# POWER_SUPPLY.net
KiCad netlist of a schematic drawn in Altium Designer
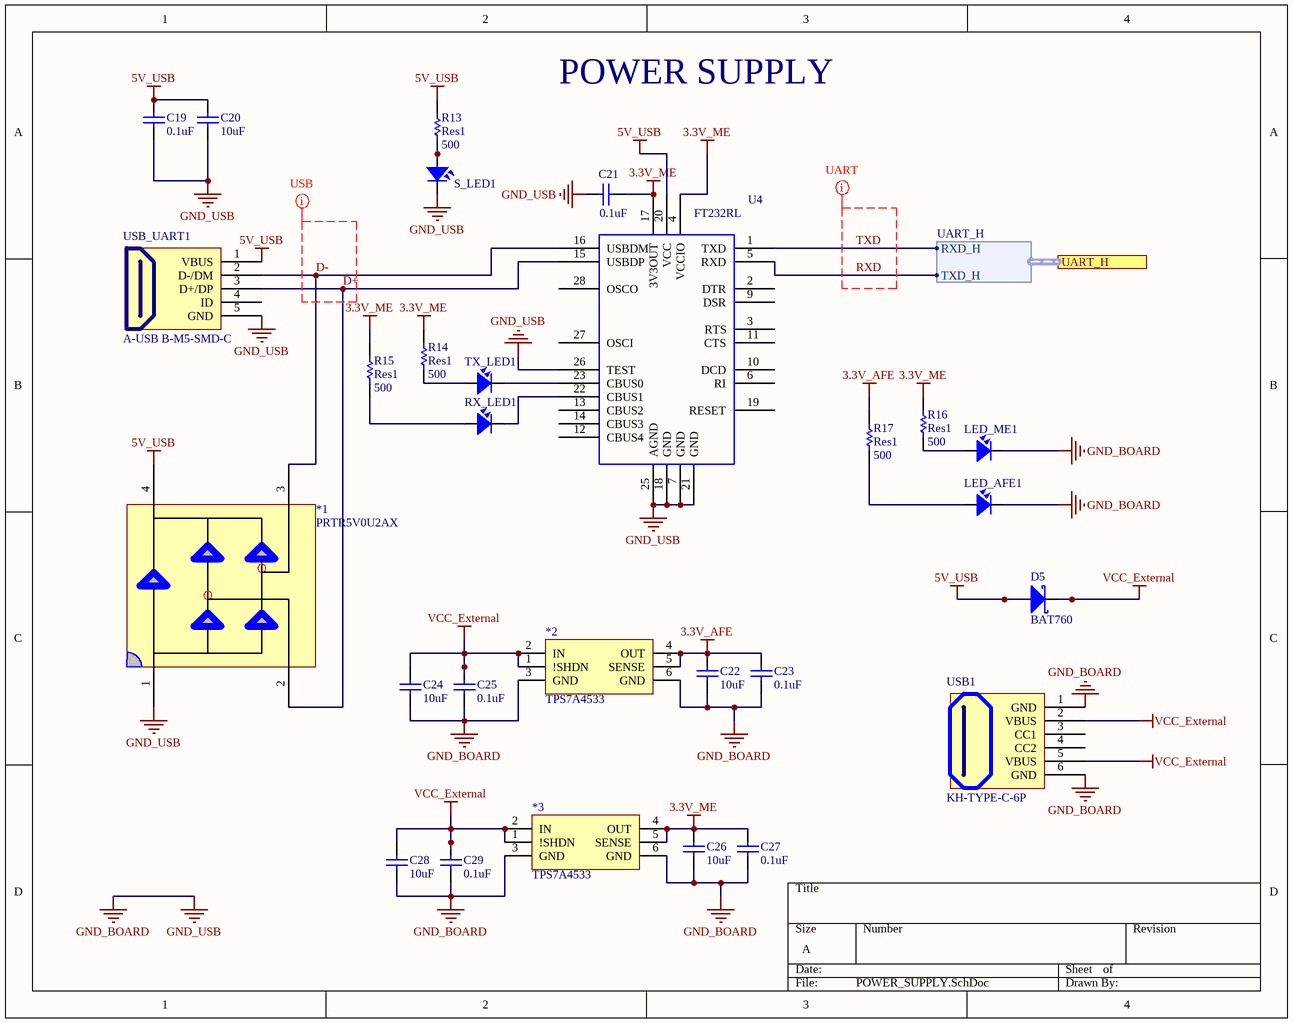
[diagram p0: POWER_SUPPLY.SchDoc]

(export (version "E")
  (design (tool "Eeschema 10.0.6"))
  (components
    (comp (ref "*1")
      (value "PRTR5V0U2AX")
      (footprint "PRTR5V0U2AX")
      (libsource (lib "Nam_SchLib") (part "PRTR5V0U2AX"))
    )
    (comp (ref "*2")
      (value "TPS7A4533")
      (footprint "SOT127P706X180-6N")
      (libsource (lib "Nam_SchLib") (part "TPS7A4501"))
    )
    (comp (ref "*3")
      (value "TPS7A4533")
      (footprint "SOT127P706X180-6N")
      (libsource (lib "Nam_SchLib") (part "TPS7A4501"))
    )
    (comp (ref "C19")
      (value "0.1uF")
      (footprint "RES-SMD-0603")
      (description "Capacitor")
      (fields (field (name "Comment") "Cap") (field (name "PUBLISHER") "Altium Limited"))
      (libsource (lib "Miscellaneous Devices") (part "Cap"))
    )
    (comp (ref "C20")
      (value "10uF")
      (footprint "RES-SMD-0603")
      (description "Capacitor")
      (fields (field (name "Comment") "Cap") (field (name "PUBLISHER") "Altium Limited"))
      (libsource (lib "Miscellaneous Devices") (part "Cap"))
    )
    (comp (ref "C21")
      (value "0.1uF")
      (footprint "RES-SMD-0603")
      (description "Capacitor")
      (fields (field (name "Comment") "Cap") (field (name "PUBLISHER") "Altium Limited"))
      (libsource (lib "Miscellaneous Devices") (part "Cap"))
    )
    (comp (ref "C22")
      (value "10uF")
      (footprint "RES-SMD-0603")
      (description "Capacitor")
      (fields (field (name "Comment") "Cap") (field (name "PUBLISHER") "Altium Limited"))
      (libsource (lib "Miscellaneous Devices") (part "Cap"))
    )
    (comp (ref "C23")
      (value "0.1uF")
      (footprint "RES-SMD-0603")
      (description "Capacitor")
      (fields (field (name "Comment") "Cap") (field (name "PUBLISHER") "Altium Limited"))
      (libsource (lib "Miscellaneous Devices") (part "Cap"))
    )
    (comp (ref "C24")
      (value "10uF")
      (footprint "RES-SMD-0603")
      (description "Capacitor")
      (fields (field (name "Comment") "Cap") (field (name "PUBLISHER") "Altium Limited"))
      (libsource (lib "Miscellaneous Devices") (part "Cap"))
    )
    (comp (ref "C25")
      (value "0.1uF")
      (footprint "RES-SMD-0603")
      (description "Capacitor")
      (fields (field (name "Comment") "Cap") (field (name "PUBLISHER") "Altium Limited"))
      (libsource (lib "Miscellaneous Devices") (part "Cap"))
    )
    (comp (ref "C26")
      (value "10uF")
      (footprint "RES-SMD-0603")
      (description "Capacitor")
      (fields (field (name "Comment") "Cap") (field (name "PUBLISHER") "Altium Limited"))
      (libsource (lib "Miscellaneous Devices") (part "Cap"))
    )
    (comp (ref "C27")
      (value "0.1uF")
      (footprint "RES-SMD-0603")
      (description "Capacitor")
      (fields (field (name "Comment") "Cap") (field (name "PUBLISHER") "Altium Limited"))
      (libsource (lib "Miscellaneous Devices") (part "Cap"))
    )
    (comp (ref "C28")
      (value "10uF")
      (footprint "RES-SMD-0603")
      (description "Capacitor")
      (fields (field (name "Comment") "Cap") (field (name "PUBLISHER") "Altium Limited"))
      (libsource (lib "Miscellaneous Devices") (part "Cap"))
    )
    (comp (ref "C29")
      (value "0.1uF")
      (footprint "RES-SMD-0603")
      (description "Capacitor")
      (fields (field (name "Comment") "Cap") (field (name "PUBLISHER") "Altium Limited"))
      (libsource (lib "Miscellaneous Devices") (part "Cap"))
    )
    (comp (ref "D5")
      (value "BAT760")
      (footprint "SOD323(F)")
      (description "Schottky Diode")
      (fields (field (name "PUBLISHER") "Altium Limited"))
      (libsource (lib "Miscellaneous Devices") (part "D Schottky"))
    )
    (comp (ref "LED_AFE1")
      (value "LED")
      (footprint "RES-SMD-0805")
      (libsource (lib "LIBRARY") (part "LED SMD"))
    )
    (comp (ref "LED_ME1")
      (value "LED")
      (footprint "RES-SMD-0805")
      (libsource (lib "LIBRARY") (part "LED SMD"))
    )
    (comp (ref "R13")
      (value "Res1")
      (footprint "RES-SMD-0603")
      (description "Resistor")
      (fields (field (name "ALTIUM_VALUE") "500") (field (name "PUBLISHER") "Altium Limited"))
      (libsource (lib "Miscellaneous Devices") (part "Res1"))
    )
    (comp (ref "R14")
      (value "Res1")
      (footprint "RES-SMD-0603")
      (description "Resistor")
      (fields (field (name "ALTIUM_VALUE") "500") (field (name "PUBLISHER") "Altium Limited"))
      (libsource (lib "Miscellaneous Devices") (part "Res1"))
    )
    (comp (ref "R15")
      (value "Res1")
      (footprint "RES-SMD-0603")
      (description "Resistor")
      (fields (field (name "ALTIUM_VALUE") "500") (field (name "PUBLISHER") "Altium Limited"))
      (libsource (lib "Miscellaneous Devices") (part "Res1"))
    )
    (comp (ref "R16")
      (value "Res1")
      (footprint "RES-SMD-0603")
      (description "Resistor")
      (fields (field (name "ALTIUM_VALUE") "500") (field (name "PUBLISHER") "Altium Limited"))
      (libsource (lib "Miscellaneous Devices") (part "Res1"))
    )
    (comp (ref "R17")
      (value "Res1")
      (footprint "RES-SMD-0603")
      (description "Resistor")
      (fields (field (name "ALTIUM_VALUE") "500") (field (name "PUBLISHER") "Altium Limited"))
      (libsource (lib "Miscellaneous Devices") (part "Res1"))
    )
    (comp (ref "RX_LED1")
      (value "LED")
      (footprint "RES-SMD-0805")
      (libsource (lib "LIBRARY") (part "LED SMD"))
    )
    (comp (ref "S_LED1")
      (value "LED")
      (footprint "RES-SMD-0805")
      (libsource (lib "LIBRARY") (part "LED SMD"))
    )
    (comp (ref "TX_LED1")
      (value "LED")
      (footprint "RES-SMD-0805")
      (libsource (lib "LIBRARY") (part "LED SMD"))
    )
    (comp (ref "U4")
      (value "FT232RL")
      (footprint "TSSOP28")
      (description "USB TO UART INTERFACE")
      (fields
        (field (name "MANUFACTURER") "FTDI, Future Technology Devices International Ltd")
        (field (name "MANUFACTURER PART NUMBER") "FT232RL R")
      )
      (libsource (lib "LIBRARY") (part "FT232RL"))
    )
    (comp (ref "USB1")
      (value "KH-TYPE-C-6P")
      (footprint "USB-typeC-6pin")
      (libsource (lib "SF_lib") (part "USB-typeC"))
    )
    (comp (ref "USB_UART1")
      (value "A-USB B-M5-SMD-C")
      (footprint "USB_B_MINI_SMD")
      (libsource (lib "electronicvn-library1") (part "USB_M"))
    )
  )
  (nets
    (net (code "2") (name "/D+") (class "Default")
      (node (ref "*1") (pin "2") (pinfunction "37_2") (pintype "passive"))
      (node (ref "U4") (pin "15") (pinfunction "USBDP_15") (pintype "passive"))
      (node (ref "USB_UART1") (pin "3") (pinfunction "D+/DP_3") (pintype "passive"))
    )
    (net (code "3") (name "/D-") (class "Default")
      (node (ref "*1") (pin "3") (pinfunction "38_3") (pintype "passive"))
      (node (ref "U4") (pin "16") (pinfunction "USBDM_16") (pintype "passive"))
      (node (ref "USB_UART1") (pin "2") (pinfunction "D-/DM_2") (pintype "passive"))
    )
    (net (code "4") (name "/RXD") (class "Default")
      (node (ref "U4") (pin "5") (pinfunction "RXD_5") (pintype "passive"))
    )
    (net (code "5") (name "/TXD") (class "Default")
      (node (ref "U4") (pin "1") (pinfunction "TXD_1") (pintype "passive"))
    )
    (net (code "7") (name "3.3V_AFE") (class "Default")
      (node (ref "*2") (pin "4") (pinfunction "OUT_4") (pintype "passive"))
      (node (ref "*2") (pin "5") (pinfunction "SENSE_5") (pintype "passive"))
      (node (ref "C22") (pin "2") (pinfunction "2_2") (pintype "passive"))
      (node (ref "C23") (pin "2") (pinfunction "2_2") (pintype "passive"))
      (node (ref "R17") (pin "2") (pinfunction "2_2") (pintype "passive"))
    )
    (net (code "8") (name "3.3V_ME") (class "Default")
      (node (ref "*3") (pin "4") (pinfunction "OUT_4") (pintype "passive"))
      (node (ref "*3") (pin "5") (pinfunction "SENSE_5") (pintype "passive"))
      (node (ref "C21") (pin "2") (pinfunction "2_2") (pintype "passive"))
      (node (ref "C26") (pin "2") (pinfunction "2_2") (pintype "passive"))
      (node (ref "C27") (pin "2") (pinfunction "2_2") (pintype "passive"))
      (node (ref "R14") (pin "2") (pinfunction "2_2") (pintype "passive"))
      (node (ref "R15") (pin "2") (pinfunction "2_2") (pintype "passive"))
      (node (ref "R16") (pin "2") (pinfunction "2_2") (pintype "passive"))
      (node (ref "U4") (pin "17") (pinfunction "3V3OUT_17") (pintype "passive"))
      (node (ref "U4") (pin "4") (pinfunction "VCCIO_4") (pintype "passive"))
    )
    (net (code "9") (name "5V_USB") (class "Default")
      (node (ref "*1") (pin "4") (pintype "passive"))
      (node (ref "C19") (pin "2") (pinfunction "2_2") (pintype "passive"))
      (node (ref "C20") (pin "1") (pinfunction "1_1") (pintype "passive"))
      (node (ref "D5") (pin "1") (pinfunction "A_1") (pintype "passive"))
      (node (ref "R13") (pin "2") (pinfunction "2_2") (pintype "passive"))
      (node (ref "U4") (pin "20") (pinfunction "VCC_20") (pintype "passive"))
      (node (ref "USB_UART1") (pin "1") (pinfunction "VBUS_1") (pintype "passive"))
    )
    (net (code "10") (name "GND_BOARD") (class "Default")
      (node (ref "*1") (pin "1") (pinfunction "36_1") (pintype "passive"))
      (node (ref "*2") (pin "3") (pinfunction "GND_3") (pintype "passive"))
      (node (ref "*2") (pin "6") (pinfunction "GND_6") (pintype "passive"))
      (node (ref "*3") (pin "3") (pinfunction "GND_3") (pintype "passive"))
      (node (ref "*3") (pin "6") (pinfunction "GND_6") (pintype "passive"))
      (node (ref "C19") (pin "1") (pinfunction "1_1") (pintype "passive"))
      (node (ref "C20") (pin "2") (pinfunction "2_2") (pintype "passive"))
      (node (ref "C21") (pin "1") (pinfunction "1_1") (pintype "passive"))
      (node (ref "C22") (pin "1") (pinfunction "1_1") (pintype "passive"))
      (node (ref "C23") (pin "1") (pinfunction "1_1") (pintype "passive"))
      (node (ref "C24") (pin "1") (pinfunction "1_1") (pintype "passive"))
      (node (ref "C25") (pin "1") (pinfunction "1_1") (pintype "passive"))
      (node (ref "C26") (pin "1") (pinfunction "1_1") (pintype "passive"))
      (node (ref "C27") (pin "1") (pinfunction "1_1") (pintype "passive"))
      (node (ref "C28") (pin "1") (pinfunction "1_1") (pintype "passive"))
      (node (ref "C29") (pin "1") (pinfunction "1_1") (pintype "passive"))
      (node (ref "LED_AFE1") (pin "2") (pinfunction "2_2") (pintype "passive"))
      (node (ref "LED_ME1") (pin "2") (pinfunction "2_2") (pintype "passive"))
      (node (ref "S_LED1") (pin "2") (pinfunction "2_2") (pintype "passive"))
      (node (ref "U4") (pin "18") (pinfunction "GND_18") (pintype "passive"))
      (node (ref "U4") (pin "21") (pinfunction "GND_21") (pintype "passive"))
      (node (ref "U4") (pin "25") (pinfunction "AGND_25") (pintype "passive"))
      (node (ref "U4") (pin "26") (pinfunction "TEST_26") (pintype "passive"))
      (node (ref "U4") (pin "7") (pinfunction "GND_7") (pintype "passive"))
      (node (ref "USB1") (pin "1") (pinfunction "GND_1") (pintype "passive"))
      (node (ref "USB1") (pin "6") (pinfunction "GND_6") (pintype "passive"))
      (node (ref "USB_UART1") (pin "5") (pinfunction "GND_5") (pintype "passive"))
    )
    (net (code "11") (name "Net-(LED_AFE1-Pad1)") (class "Default")
      (node (ref "LED_AFE1") (pin "1") (pinfunction "1_1") (pintype "passive"))
      (node (ref "R17") (pin "1") (pinfunction "1_1") (pintype "passive"))
    )
    (net (code "12") (name "Net-(LED_ME1-Pad1)") (class "Default")
      (node (ref "LED_ME1") (pin "1") (pinfunction "1_1") (pintype "passive"))
      (node (ref "R16") (pin "1") (pinfunction "1_1") (pintype "passive"))
    )
    (net (code "13") (name "Net-(R13-Pad1)") (class "Default")
      (node (ref "R13") (pin "1") (pinfunction "1_1") (pintype "passive"))
      (node (ref "S_LED1") (pin "1") (pinfunction "1_1") (pintype "passive"))
    )
    (net (code "14") (name "Net-(R14-Pad1)") (class "Default")
      (node (ref "R14") (pin "1") (pinfunction "1_1") (pintype "passive"))
      (node (ref "TX_LED1") (pin "1") (pinfunction "1_1") (pintype "passive"))
    )
    (net (code "15") (name "Net-(R15-Pad1)") (class "Default")
      (node (ref "R15") (pin "1") (pinfunction "1_1") (pintype "passive"))
      (node (ref "RX_LED1") (pin "1") (pinfunction "1_1") (pintype "passive"))
    )
    (net (code "16") (name "Net-(U4-CBUS0)") (class "Default")
      (node (ref "TX_LED1") (pin "2") (pinfunction "2_2") (pintype "passive"))
      (node (ref "U4") (pin "23") (pinfunction "CBUS0_23") (pintype "passive"))
    )
    (net (code "17") (name "Net-(U4-CBUS1)") (class "Default")
      (node (ref "RX_LED1") (pin "2") (pinfunction "2_2") (pintype "passive"))
      (node (ref "U4") (pin "22") (pinfunction "CBUS1_22") (pintype "passive"))
    )
    (net (code "18") (name "VCC_External") (class "Default")
      (node (ref "*2") (pin "1") (pinfunction "!SHDN_1") (pintype "passive"))
      (node (ref "*2") (pin "2") (pinfunction "IN_2") (pintype "passive"))
      (node (ref "*3") (pin "1") (pinfunction "!SHDN_1") (pintype "passive"))
      (node (ref "*3") (pin "2") (pinfunction "IN_2") (pintype "passive"))
      (node (ref "C24") (pin "2") (pinfunction "2_2") (pintype "passive"))
      (node (ref "C25") (pin "2") (pinfunction "2_2") (pintype "passive"))
      (node (ref "C28") (pin "2") (pinfunction "2_2") (pintype "passive"))
      (node (ref "C29") (pin "2") (pinfunction "2_2") (pintype "passive"))
      (node (ref "D5") (pin "2") (pinfunction "K_2") (pintype "passive"))
      (node (ref "USB1") (pin "2") (pinfunction "VBUS_2") (pintype "passive"))
      (node (ref "USB1") (pin "5") (pinfunction "VBUS_5") (pintype "passive"))
    )
    (net (code "19") (name "unconnected-(U4-CBUS2-Pad13)") (class "Default")
      (node (ref "U4") (pin "13") (pinfunction "CBUS2_13") (pintype "passive"))
    )
    (net (code "20") (name "unconnected-(U4-CBUS3-Pad14)") (class "Default")
      (node (ref "U4") (pin "14") (pinfunction "CBUS3_14") (pintype "passive"))
    )
    (net (code "21") (name "unconnected-(U4-CBUS4-Pad12)") (class "Default")
      (node (ref "U4") (pin "12") (pinfunction "CBUS4_12") (pintype "passive"))
    )
    (net (code "22") (name "unconnected-(U4-CTS-Pad11)") (class "Default")
      (node (ref "U4") (pin "11") (pinfunction "CTS_11") (pintype "passive"))
    )
    (net (code "23") (name "unconnected-(U4-DCD-Pad10)") (class "Default")
      (node (ref "U4") (pin "10") (pinfunction "DCD_10") (pintype "passive"))
    )
    (net (code "24") (name "unconnected-(U4-DSR-Pad9)") (class "Default")
      (node (ref "U4") (pin "9") (pinfunction "DSR_9") (pintype "passive"))
    )
    (net (code "25") (name "unconnected-(U4-DTR-Pad2)") (class "Default")
      (node (ref "U4") (pin "2") (pinfunction "DTR_2") (pintype "passive"))
    )
    (net (code "26") (name "unconnected-(U4-OSCI-Pad27)") (class "Default")
      (node (ref "U4") (pin "27") (pinfunction "OSCI_27") (pintype "passive"))
    )
    (net (code "27") (name "unconnected-(U4-OSCO-Pad28)") (class "Default")
      (node (ref "U4") (pin "28") (pinfunction "OSCO_28") (pintype "passive"))
    )
    (net (code "28") (name "unconnected-(U4-RESET-Pad19)") (class "Default")
      (node (ref "U4") (pin "19") (pinfunction "RESET_19") (pintype "passive"))
    )
    (net (code "29") (name "unconnected-(U4-RI-Pad6)") (class "Default")
      (node (ref "U4") (pin "6") (pinfunction "RI_6") (pintype "passive"))
    )
    (net (code "30") (name "unconnected-(U4-RTS-Pad3)") (class "Default")
      (node (ref "U4") (pin "3") (pinfunction "RTS_3") (pintype "passive"))
    )
    (net (code "31") (name "unconnected-(USB1-CC1-Pad3)") (class "Default")
      (node (ref "USB1") (pin "3") (pinfunction "CC1_3") (pintype "passive"))
    )
    (net (code "32") (name "unconnected-(USB1-CC2-Pad4)") (class "Default")
      (node (ref "USB1") (pin "4") (pinfunction "CC2_4") (pintype "passive"))
    )
    (net (code "33") (name "unconnected-(USB_UART1-ID-Pad4)") (class "Default")
      (node (ref "USB_UART1") (pin "4") (pinfunction "ID_4") (pintype "passive"))
    )
  )
)
